# P2N15-001.net
KiCad netlist of a schematic drawn in EAGLE
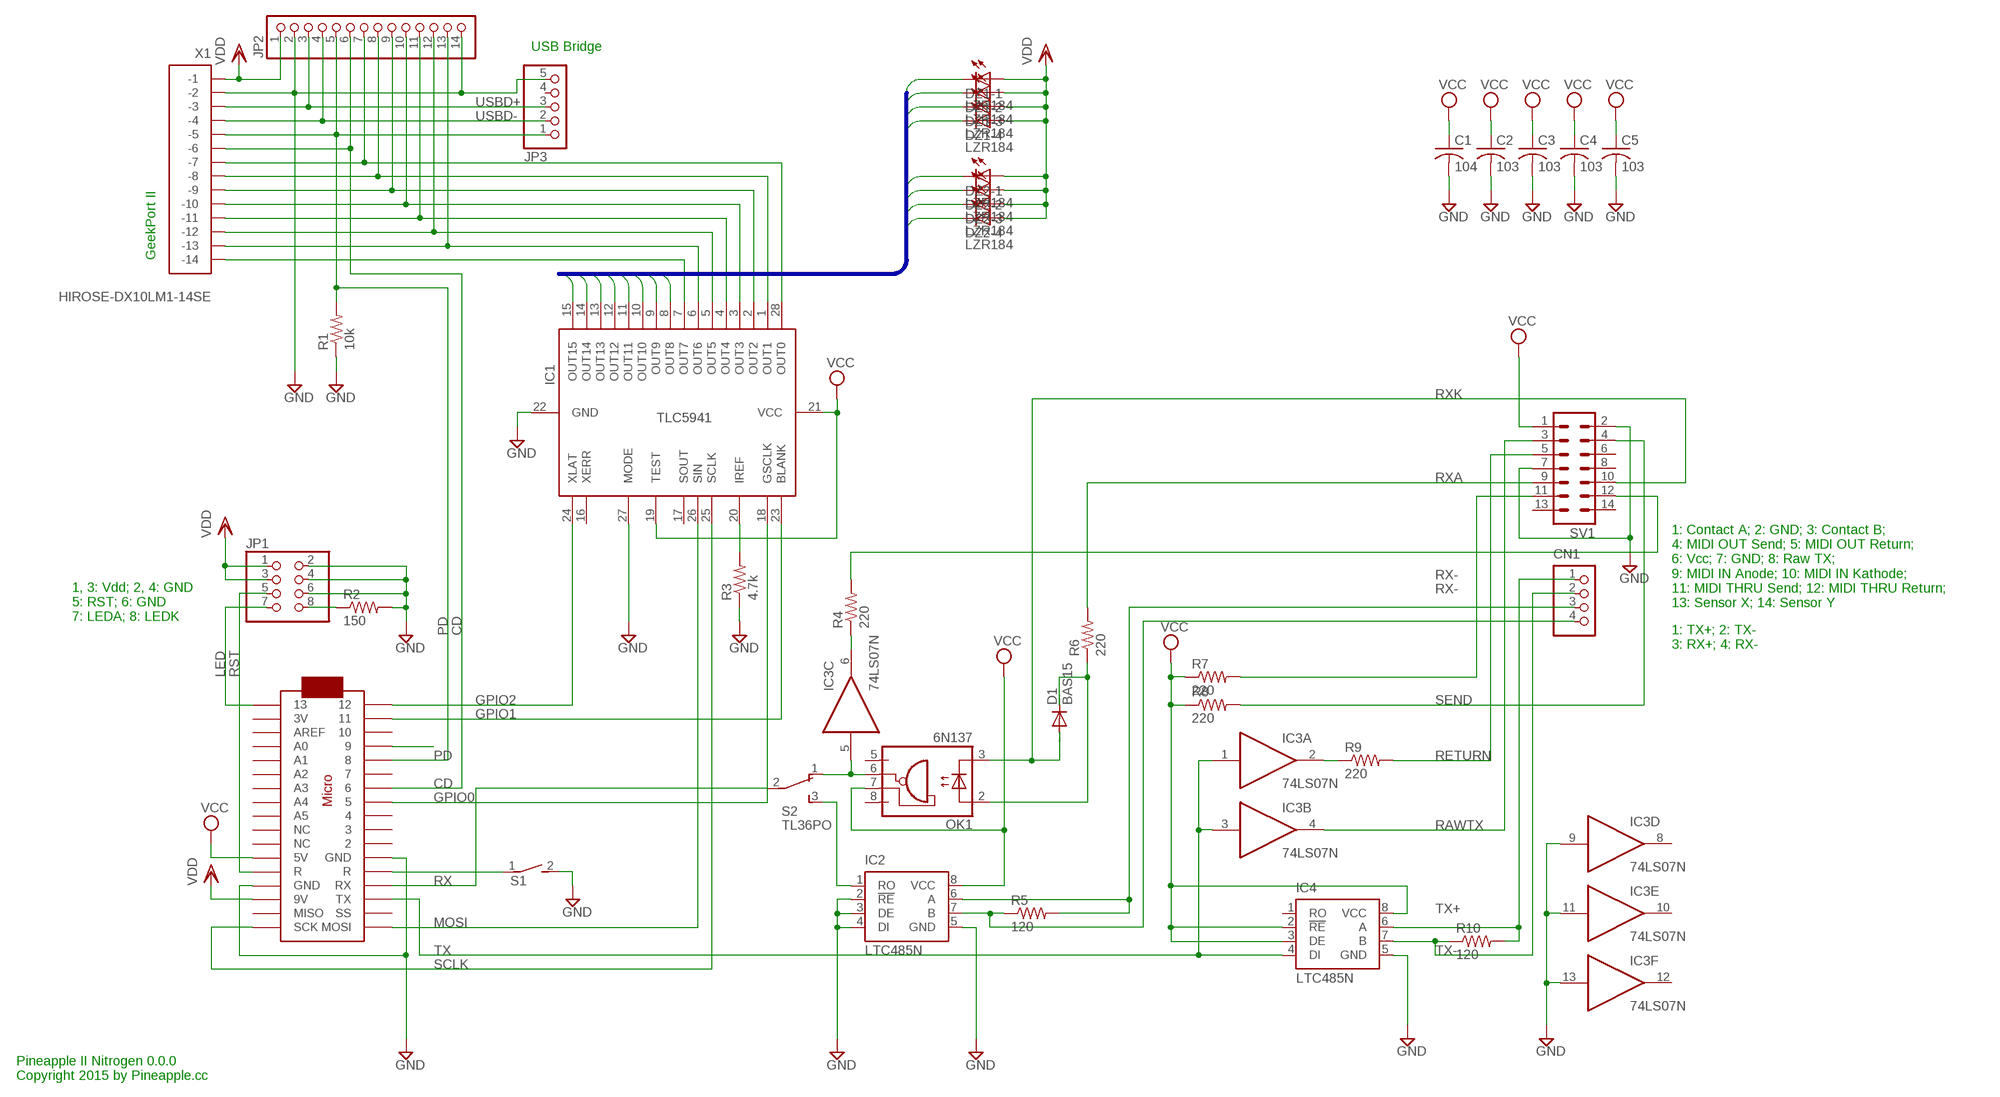
[diagram p0: schematic, sheet 1]

(export (version "E")
  (design (tool "Eeschema 10.0.6"))
  (components
    (comp (ref "C1")
      (value "104")
      (footprint "eagle-import:C025-025X050")
      (libsource (lib "eagle-import") (part "C-US025-025X050"))
    )
    (comp (ref "C2")
      (value "103")
      (footprint "eagle-import:C025-025X050")
      (libsource (lib "eagle-import") (part "C-US025-025X050"))
    )
    (comp (ref "C3")
      (value "103")
      (footprint "eagle-import:C025-025X050")
      (libsource (lib "eagle-import") (part "C-US025-025X050"))
    )
    (comp (ref "C4")
      (value "103")
      (footprint "eagle-import:C025-025X050")
      (libsource (lib "eagle-import") (part "C-US025-025X050"))
    )
    (comp (ref "C5")
      (value "103")
      (footprint "eagle-import:C025-025X050")
      (libsource (lib "eagle-import") (part "C-US025-025X050"))
    )
    (comp (ref "CN1")
      (value "S4B-PH-K-S")
      (footprint "eagle-import:S4B-PH-K-S")
      (libsource (lib "eagle-import") (part "S4B-PH-K-S"))
    )
    (comp (ref "D1")
      (value "BAS15")
      (footprint "eagle-import:DO34-7")
      (libsource (lib "eagle-import") (part "BAS15"))
    )
    (comp (ref "DZ1")
      (value "LZR184")
      (footprint "eagle-import:LZR184")
      (libsource (lib "eagle-import") (part "LZR184"))
    )
    (comp (ref "DZ2")
      (value "LZR184")
      (footprint "eagle-import:LZR184")
      (libsource (lib "eagle-import") (part "LZR184"))
    )
    (comp (ref "IC1")
      (value "TLC5941NT")
      (footprint "eagle-import:DIL28-3")
      (libsource (lib "eagle-import") (part "TLC5941NT"))
    )
    (comp (ref "IC2")
      (value "LTC485N")
      (footprint "eagle-import:DIL08")
      (libsource (lib "eagle-import") (part "LTC485N"))
    )
    (comp (ref "IC3")
      (value "74LS07N")
      (footprint "eagle-import:DIL14")
      (libsource (lib "eagle-import") (part "7407NLS"))
    )
    (comp (ref "IC4")
      (value "LTC485N")
      (footprint "eagle-import:DIL08")
      (libsource (lib "eagle-import") (part "LTC485N"))
    )
    (comp (ref "JP1")
      (value "PINHD-2X4")
      (footprint "eagle-import:2X04")
      (libsource (lib "eagle-import") (part "PINHD-2X4"))
    )
    (comp (ref "JP2")
      (value "PINHD-1X14")
      (footprint "eagle-import:1X14")
      (libsource (lib "eagle-import") (part "PINHD-1X14"))
    )
    (comp (ref "JP3")
      (value "PINHD-1X5/90")
      (footprint "eagle-import:1X05_90")
      (libsource (lib "eagle-import") (part "PINHD-1X5/90"))
    )
    (comp (ref "MC1")
      (value "ARDUINOMICRO")
      (footprint "eagle-import:ARDUINOMICRO")
      (libsource (lib "eagle-import") (part "ARDUINOMICRO"))
    )
    (comp (ref "OK1")
      (value "6N137")
      (footprint "eagle-import:DIL08")
      (libsource (lib "eagle-import") (part "6N137"))
    )
    (comp (ref "R1")
      (value "10k")
      (footprint "eagle-import:0204_5")
      (libsource (lib "eagle-import") (part "R-US_0204/5"))
    )
    (comp (ref "R2")
      (value "150")
      (footprint "eagle-import:0204_5")
      (libsource (lib "eagle-import") (part "R-US_0204/5"))
    )
    (comp (ref "R3")
      (value "4.7k")
      (footprint "eagle-import:0204_5")
      (libsource (lib "eagle-import") (part "R-US_0204/5"))
    )
    (comp (ref "R4")
      (value "220")
      (footprint "eagle-import:0204_5")
      (libsource (lib "eagle-import") (part "R-US_0204/5"))
    )
    (comp (ref "R5")
      (value "120")
      (footprint "eagle-import:0204_5")
      (libsource (lib "eagle-import") (part "R-US_0204/5"))
    )
    (comp (ref "R6")
      (value "220")
      (footprint "eagle-import:0204_5")
      (libsource (lib "eagle-import") (part "R-US_0204/5"))
    )
    (comp (ref "R7")
      (value "220")
      (footprint "eagle-import:0204_5")
      (libsource (lib "eagle-import") (part "R-US_0204/5"))
    )
    (comp (ref "R8")
      (value "220")
      (footprint "eagle-import:0204_5")
      (libsource (lib "eagle-import") (part "R-US_0204/5"))
    )
    (comp (ref "R9")
      (value "220")
      (footprint "eagle-import:0204_5")
      (libsource (lib "eagle-import") (part "R-US_0204/5"))
    )
    (comp (ref "R10")
      (value "120")
      (footprint "eagle-import:0204_5")
      (libsource (lib "eagle-import") (part "R-US_0204/5"))
    )
    (comp (ref "S1")
      (value "DS01E")
      (footprint "eagle-import:DS-01")
      (libsource (lib "eagle-import") (part "DS01E"))
    )
    (comp (ref "S2")
      (value "TL36PO")
      (footprint "eagle-import:TL3XPO")
      (libsource (lib "eagle-import") (part "TL36PO"))
    )
    (comp (ref "SV1")
      (value "ML14L")
      (footprint "eagle-import:ML14L")
      (libsource (lib "eagle-import") (part "ML14L"))
    )
    (comp (ref "X1")
      (value "HIROSE-DX10LM1-14SE")
      (footprint "eagle-import:HIROSE-DX10LM1-14SE")
      (fields (field (name "MPN") "AXR30545"))
      (libsource (lib "eagle-import") (part "HIROSE-DX10LM1-14SE"))
    )
  )
  (nets
    (net (code "1") (name "/CD") (class "Default")
      (node (ref "JP2") (pin "6") (pinfunction "6_6") (pintype "passive"))
      (node (ref "MC1") (pin "P$7") (pinfunction "6_P$7") (pintype "bidirectional"))
      (node (ref "X1") (pin "P$6") (pinfunction "-6_P$6") (pintype "input"))
    )
    (net (code "2") (name "/GPIO0") (class "Default")
      (node (ref "IC1") (pin "18") (pinfunction "GSCLK_18") (pintype "input"))
      (node (ref "MC1") (pin "P$8") (pinfunction "5_P$8") (pintype "bidirectional"))
    )
    (net (code "3") (name "/GPIO1") (class "Default")
      (node (ref "IC1") (pin "23") (pinfunction "BLANK_23") (pintype "input"))
      (node (ref "MC1") (pin "P$2") (pinfunction "11_P$2") (pintype "bidirectional"))
    )
    (net (code "4") (name "/GPIO2") (class "Default")
      (node (ref "IC1") (pin "24") (pinfunction "XLAT_24") (pintype "input"))
      (node (ref "MC1") (pin "P$1") (pinfunction "12_P$1") (pintype "bidirectional"))
    )
    (net (code "5") (name "/LED") (class "Default")
      (node (ref "JP1") (pin "7") (pinfunction "7_7") (pintype "passive"))
      (node (ref "MC1") (pin "P$34") (pinfunction "13_P$34") (pintype "bidirectional"))
    )
    (net (code "6") (name "/LED0") (class "Default")
      (node (ref "DZ1") (pin "K1") (pinfunction "C_K1") (pintype "passive"))
      (node (ref "IC1") (pin "8") (pinfunction "OUT8_8") (pintype "output"))
    )
    (net (code "7") (name "/LED1") (class "Default")
      (node (ref "DZ1") (pin "K2") (pinfunction "C_K2") (pintype "passive"))
      (node (ref "IC1") (pin "9") (pinfunction "OUT9_9") (pintype "output"))
    )
    (net (code "8") (name "/LED2") (class "Default")
      (node (ref "DZ1") (pin "K3") (pinfunction "C_K3") (pintype "passive"))
      (node (ref "IC1") (pin "10") (pinfunction "OUT10_10") (pintype "output"))
    )
    (net (code "9") (name "/LED3") (class "Default")
      (node (ref "DZ1") (pin "K4") (pinfunction "C_K4") (pintype "passive"))
      (node (ref "IC1") (pin "11") (pinfunction "OUT11_11") (pintype "output"))
    )
    (net (code "10") (name "/LED4") (class "Default")
      (node (ref "DZ2") (pin "K1") (pinfunction "C_K1") (pintype "passive"))
      (node (ref "IC1") (pin "12") (pinfunction "OUT12_12") (pintype "output"))
    )
    (net (code "11") (name "/LED5") (class "Default")
      (node (ref "DZ2") (pin "K2") (pinfunction "C_K2") (pintype "passive"))
      (node (ref "IC1") (pin "13") (pinfunction "OUT13_13") (pintype "output"))
    )
    (net (code "12") (name "/LED6") (class "Default")
      (node (ref "DZ2") (pin "K3") (pinfunction "C_K3") (pintype "passive"))
      (node (ref "IC1") (pin "14") (pinfunction "OUT14_14") (pintype "output"))
    )
    (net (code "13") (name "/LED7") (class "Default")
      (node (ref "DZ2") (pin "K4") (pinfunction "C_K4") (pintype "passive"))
      (node (ref "IC1") (pin "15") (pinfunction "OUT15_15") (pintype "output"))
    )
    (net (code "14") (name "/MOSI") (class "Default")
      (node (ref "IC1") (pin "26") (pinfunction "SIN_26") (pintype "input"))
      (node (ref "MC1") (pin "P$17") (pinfunction "MOSI_P$17") (pintype "bidirectional"))
    )
    (net (code "15") (name "/PD") (class "Default")
      (node (ref "JP2") (pin "5") (pinfunction "5_5") (pintype "passive"))
      (node (ref "JP3") (pin "1") (pinfunction "1_1") (pintype "passive"))
      (node (ref "MC1") (pin "P$5") (pinfunction "8_P$5") (pintype "bidirectional"))
      (node (ref "R1") (pin "2") (pinfunction "2_2") (pintype "passive"))
      (node (ref "X1") (pin "P$5") (pinfunction "-5_P$5") (pintype "input"))
    )
    (net (code "16") (name "/RAWTX") (class "Default")
      (node (ref "IC3") (pin "4") (pinfunction "O_4") (pintype "open_collector"))
      (node (ref "SV1") (pin "3") (pinfunction "3_3") (pintype "passive"))
    )
    (net (code "17") (name "/RETURN") (class "Default")
      (node (ref "R9") (pin "2") (pinfunction "2_2") (pintype "passive"))
      (node (ref "SV1") (pin "5") (pinfunction "5_5") (pintype "passive"))
    )
    (net (code "18") (name "/RST") (class "Default")
      (node (ref "JP1") (pin "5") (pinfunction "5_5") (pintype "passive"))
      (node (ref "MC1") (pin "P$13") (pinfunction "R_P$13") (pintype "bidirectional"))
    )
    (net (code "19") (name "/RX") (class "Default")
      (node (ref "MC1") (pin "P$14") (pinfunction "RX_P$14") (pintype "bidirectional"))
      (node (ref "S2") (pin "2") (pinfunction "P_2") (pintype "passive"))
    )
    (net (code "20") (name "/RX-") (class "Default")
      (node (ref "CN1") (pin "4") (pinfunction "4_4") (pintype "passive"))
      (node (ref "IC2") (pin "7") (pinfunction "B_7") (pintype "bidirectional"))
      (node (ref "R5") (pin "1") (pinfunction "1_1") (pintype "passive"))
    )
    (net (code "21") (name "/RXA") (class "Default")
      (node (ref "R6") (pin "2") (pinfunction "2_2") (pintype "passive"))
      (node (ref "SV1") (pin "9") (pinfunction "9_9") (pintype "passive"))
    )
    (net (code "22") (name "/RXK") (class "Default")
      (node (ref "D1") (pin "A") (pinfunction "A_A") (pintype "passive"))
      (node (ref "OK1") (pin "3") (pinfunction "C_3") (pintype "passive"))
      (node (ref "SV1") (pin "10") (pinfunction "10_10") (pintype "passive"))
    )
    (net (code "23") (name "/SCLK") (class "Default")
      (node (ref "IC1") (pin "25") (pinfunction "SCLK_25") (pintype "input"))
      (node (ref "MC1") (pin "P$18") (pinfunction "SCK_P$18") (pintype "bidirectional"))
    )
    (net (code "24") (name "/SEND") (class "Default")
      (node (ref "R8") (pin "2") (pinfunction "2_2") (pintype "passive"))
      (node (ref "SV1") (pin "4") (pinfunction "4_4") (pintype "passive"))
    )
    (net (code "25") (name "/TX") (class "Default")
      (node (ref "IC3") (pin "1") (pinfunction "I_1") (pintype "input"))
      (node (ref "IC3") (pin "3") (pinfunction "I_3") (pintype "input"))
      (node (ref "IC4") (pin "4") (pinfunction "DI_4") (pintype "input"))
      (node (ref "MC1") (pin "P$15") (pinfunction "TX_P$15") (pintype "bidirectional"))
    )
    (net (code "26") (name "/TX+") (class "Default")
      (node (ref "CN1") (pin "1") (pinfunction "1_1") (pintype "passive"))
      (node (ref "IC4") (pin "6") (pinfunction "A_6") (pintype "bidirectional"))
      (node (ref "R10") (pin "2") (pinfunction "2_2") (pintype "passive"))
    )
    (net (code "27") (name "/TX-") (class "Default")
      (node (ref "CN1") (pin "2") (pinfunction "2_2") (pintype "passive"))
      (node (ref "IC4") (pin "7") (pinfunction "B_7") (pintype "bidirectional"))
      (node (ref "R10") (pin "1") (pinfunction "1_1") (pintype "passive"))
    )
    (net (code "28") (name "/USBD+") (class "Default")
      (node (ref "JP2") (pin "3") (pinfunction "3_3") (pintype "passive"))
      (node (ref "JP3") (pin "3") (pinfunction "3_3") (pintype "passive"))
      (node (ref "X1") (pin "P$3") (pinfunction "-3_P$3") (pintype "input"))
    )
    (net (code "29") (name "/USBD-") (class "Default")
      (node (ref "JP2") (pin "4") (pinfunction "4_4") (pintype "passive"))
      (node (ref "JP3") (pin "2") (pinfunction "2_2") (pintype "passive"))
      (node (ref "X1") (pin "P$4") (pinfunction "-4_P$4") (pintype "input"))
    )
    (net (code "30") (name "GND") (class "Default")
      (node (ref "C1") (pin "2") (pinfunction "2_2") (pintype "passive"))
      (node (ref "C2") (pin "2") (pinfunction "2_2") (pintype "passive"))
      (node (ref "C3") (pin "2") (pinfunction "2_2") (pintype "passive"))
      (node (ref "C4") (pin "2") (pinfunction "2_2") (pintype "passive"))
      (node (ref "C5") (pin "2") (pinfunction "2_2") (pintype "passive"))
      (node (ref "IC1") (pin "22") (pinfunction "GND_22") (pintype "power_in"))
      (node (ref "IC1") (pin "27") (pinfunction "MODE_27") (pintype "input"))
      (node (ref "IC2") (pin "2") (pinfunction "~{RE}_2") (pintype "input"))
      (node (ref "IC2") (pin "3") (pinfunction "DE_3") (pintype "input"))
      (node (ref "IC2") (pin "4") (pinfunction "DI_4") (pintype "input"))
      (node (ref "IC2") (pin "5") (pinfunction "GND_5") (pintype "input"))
      (node (ref "IC3") (pin "11") (pinfunction "I_11") (pintype "input"))
      (node (ref "IC3") (pin "13") (pinfunction "I_13") (pintype "input"))
      (node (ref "IC3") (pin "9") (pinfunction "I_9") (pintype "input"))
      (node (ref "IC4") (pin "5") (pinfunction "GND_5") (pintype "input"))
      (node (ref "JP1") (pin "2") (pinfunction "2_2") (pintype "passive"))
      (node (ref "JP1") (pin "4") (pinfunction "4_4") (pintype "passive"))
      (node (ref "JP1") (pin "6") (pinfunction "6_6") (pintype "passive"))
      (node (ref "JP2") (pin "14") (pinfunction "14_14") (pintype "passive"))
      (node (ref "JP2") (pin "2") (pinfunction "2_2") (pintype "passive"))
      (node (ref "JP3") (pin "5") (pinfunction "5_5") (pintype "passive"))
      (node (ref "MC1") (pin "P$12") (pinfunction "GND_P$12") (pintype "bidirectional"))
      (node (ref "MC1") (pin "P$21") (pinfunction "GND_P$21") (pintype "bidirectional"))
      (node (ref "R1") (pin "1") (pinfunction "1_1") (pintype "passive"))
      (node (ref "R2") (pin "2") (pinfunction "2_2") (pintype "passive"))
      (node (ref "R3") (pin "1") (pinfunction "1_1") (pintype "passive"))
      (node (ref "S1") (pin "2") (pinfunction "2_2") (pintype "passive"))
      (node (ref "SV1") (pin "2") (pinfunction "2_2") (pintype "passive"))
      (node (ref "SV1") (pin "7") (pinfunction "7_7") (pintype "passive"))
      (node (ref "X1") (pin "P$2") (pinfunction "-2_P$2") (pintype "input"))
    )
    (net (code "31") (name "Net-(IC1-IREF)") (class "Default")
      (node (ref "IC1") (pin "20") (pinfunction "IREF_20") (pintype "bidirectional"))
      (node (ref "R3") (pin "2") (pinfunction "2_2") (pintype "passive"))
    )
    (net (code "32") (name "Net-(IC1-OUT0)") (class "Default")
      (node (ref "IC1") (pin "28") (pinfunction "OUT0_28") (pintype "output"))
      (node (ref "JP2") (pin "7") (pinfunction "7_7") (pintype "passive"))
      (node (ref "X1") (pin "P$7") (pinfunction "-7_P$7") (pintype "input"))
    )
    (net (code "33") (name "Net-(IC1-OUT1)") (class "Default")
      (node (ref "IC1") (pin "1") (pinfunction "OUT1_1") (pintype "output"))
      (node (ref "JP2") (pin "8") (pinfunction "8_8") (pintype "passive"))
      (node (ref "X1") (pin "P$8") (pinfunction "-8_P$8") (pintype "input"))
    )
    (net (code "34") (name "Net-(IC1-OUT2)") (class "Default")
      (node (ref "IC1") (pin "2") (pinfunction "OUT2_2") (pintype "output"))
      (node (ref "JP2") (pin "9") (pinfunction "9_9") (pintype "passive"))
      (node (ref "X1") (pin "P$9") (pinfunction "-9_P$9") (pintype "input"))
    )
    (net (code "35") (name "Net-(IC1-OUT3)") (class "Default")
      (node (ref "IC1") (pin "3") (pinfunction "OUT3_3") (pintype "output"))
      (node (ref "JP2") (pin "10") (pinfunction "10_10") (pintype "passive"))
      (node (ref "X1") (pin "P$10") (pinfunction "-10_P$10") (pintype "input"))
    )
    (net (code "36") (name "Net-(IC1-OUT4)") (class "Default")
      (node (ref "IC1") (pin "4") (pinfunction "OUT4_4") (pintype "output"))
      (node (ref "JP2") (pin "11") (pinfunction "11_11") (pintype "passive"))
      (node (ref "X1") (pin "P$11") (pinfunction "-11_P$11") (pintype "input"))
    )
    (net (code "37") (name "Net-(IC1-OUT5)") (class "Default")
      (node (ref "IC1") (pin "5") (pinfunction "OUT5_5") (pintype "output"))
      (node (ref "JP2") (pin "12") (pinfunction "12_12") (pintype "passive"))
      (node (ref "X1") (pin "P$12") (pinfunction "-12_P$12") (pintype "input"))
    )
    (net (code "38") (name "Net-(IC1-OUT6)") (class "Default")
      (node (ref "IC1") (pin "6") (pinfunction "OUT6_6") (pintype "output"))
      (node (ref "JP2") (pin "13") (pinfunction "13_13") (pintype "passive"))
      (node (ref "X1") (pin "P$13") (pinfunction "-13_P$13") (pintype "input"))
    )
    (net (code "39") (name "Net-(IC1-OUT7)") (class "Default")
      (node (ref "IC1") (pin "7") (pinfunction "OUT7_7") (pintype "output"))
      (node (ref "X1") (pin "P$14") (pinfunction "-14_P$14") (pintype "input"))
    )
    (net (code "40") (name "Net-(IC2-A)") (class "Default")
      (node (ref "CN1") (pin "3") (pinfunction "3_3") (pintype "passive"))
      (node (ref "IC2") (pin "6") (pinfunction "A_6") (pintype "bidirectional"))
      (node (ref "R5") (pin "2") (pinfunction "2_2") (pintype "passive"))
    )
    (net (code "41") (name "Net-(IC2-RO)") (class "Default")
      (node (ref "IC2") (pin "1") (pinfunction "RO_1") (pintype "output"))
      (node (ref "S2") (pin "3") (pinfunction "S_3") (pintype "passive"))
    )
    (net (code "42") (name "Net-(IC3A-O)") (class "Default")
      (node (ref "IC3") (pin "2") (pinfunction "O_2") (pintype "open_collector"))
      (node (ref "R9") (pin "1") (pinfunction "1_1") (pintype "passive"))
    )
    (net (code "43") (name "Net-(IC3C-I)") (class "Default")
      (node (ref "IC3") (pin "5") (pinfunction "I_5") (pintype "input"))
      (node (ref "OK1") (pin "6") (pinfunction "VO_6") (pintype "passive"))
      (node (ref "S2") (pin "1") (pinfunction "O_1") (pintype "passive"))
    )
    (net (code "44") (name "Net-(IC3C-O)") (class "Default")
      (node (ref "IC3") (pin "6") (pinfunction "O_6") (pintype "open_collector"))
      (node (ref "R4") (pin "1") (pinfunction "1_1") (pintype "passive"))
    )
    (net (code "45") (name "Net-(JP1-Pad8)") (class "Default")
      (node (ref "JP1") (pin "8") (pinfunction "8_8") (pintype "passive"))
      (node (ref "R2") (pin "1") (pinfunction "1_1") (pintype "passive"))
    )
    (net (code "46") (name "Net-(MC1-R-PadP$22)") (class "Default")
      (node (ref "MC1") (pin "P$22") (pinfunction "R_P$22") (pintype "bidirectional"))
      (node (ref "S1") (pin "1") (pinfunction "1_1") (pintype "passive"))
    )
    (net (code "47") (name "Net-(OK1-A)") (class "Default")
      (node (ref "D1") (pin "C") (pinfunction "C_C") (pintype "passive"))
      (node (ref "OK1") (pin "2") (pinfunction "A_2") (pintype "passive"))
      (node (ref "R6") (pin "1") (pinfunction "1_1") (pintype "passive"))
    )
    (net (code "48") (name "Net-(R4-Pad2)") (class "Default")
      (node (ref "R4") (pin "2") (pinfunction "2_2") (pintype "passive"))
      (node (ref "SV1") (pin "12") (pinfunction "12_12") (pintype "passive"))
    )
    (net (code "49") (name "Net-(R7-Pad2)") (class "Default")
      (node (ref "R7") (pin "2") (pinfunction "2_2") (pintype "passive"))
      (node (ref "SV1") (pin "11") (pinfunction "11_11") (pintype "passive"))
    )
    (net (code "50") (name "VCC") (class "Default")
      (node (ref "C1") (pin "1") (pinfunction "1_1") (pintype "passive"))
      (node (ref "C2") (pin "1") (pinfunction "1_1") (pintype "passive"))
      (node (ref "C3") (pin "1") (pinfunction "1_1") (pintype "passive"))
      (node (ref "C4") (pin "1") (pinfunction "1_1") (pintype "passive"))
      (node (ref "C5") (pin "1") (pinfunction "1_1") (pintype "passive"))
      (node (ref "IC1") (pin "19") (pinfunction "TEST_19") (pintype "input"))
      (node (ref "IC1") (pin "21") (pinfunction "VCC_21") (pintype "power_in"))
      (node (ref "IC2") (pin "8") (pinfunction "VCC_8") (pintype "input"))
      (node (ref "IC4") (pin "2") (pinfunction "~{RE}_2") (pintype "input"))
      (node (ref "IC4") (pin "3") (pinfunction "DE_3") (pintype "input"))
      (node (ref "IC4") (pin "8") (pinfunction "VCC_8") (pintype "input"))
      (node (ref "MC1") (pin "P$23") (pinfunction "5V_P$23") (pintype "bidirectional"))
      (node (ref "OK1") (pin "7") (pinfunction "VE_7") (pintype "passive"))
      (node (ref "R7") (pin "1") (pinfunction "1_1") (pintype "passive"))
      (node (ref "R8") (pin "1") (pinfunction "1_1") (pintype "passive"))
      (node (ref "SV1") (pin "1") (pinfunction "1_1") (pintype "passive"))
    )
    (net (code "51") (name "VDD") (class "Default")
      (node (ref "DZ1") (pin "A1") (pinfunction "A_A1") (pintype "passive"))
      (node (ref "DZ1") (pin "A2") (pinfunction "A_A2") (pintype "passive"))
      (node (ref "DZ1") (pin "A3") (pinfunction "A_A3") (pintype "passive"))
      (node (ref "DZ1") (pin "A4") (pinfunction "A_A4") (pintype "passive"))
      (node (ref "DZ2") (pin "A1") (pinfunction "A_A1") (pintype "passive"))
      (node (ref "DZ2") (pin "A2") (pinfunction "A_A2") (pintype "passive"))
      (node (ref "DZ2") (pin "A3") (pinfunction "A_A3") (pintype "passive"))
      (node (ref "DZ2") (pin "A4") (pinfunction "A_A4") (pintype "passive"))
      (node (ref "JP1") (pin "1") (pinfunction "1_1") (pintype "passive"))
      (node (ref "JP1") (pin "3") (pinfunction "3_3") (pintype "passive"))
      (node (ref "JP2") (pin "1") (pinfunction "1_1") (pintype "passive"))
      (node (ref "MC1") (pin "P$20") (pinfunction "9V_P$20") (pintype "bidirectional"))
      (node (ref "X1") (pin "P$1") (pinfunction "-1_P$1") (pintype "input"))
    )
    (net (code "52") (name "unconnected-(IC1-SOUT-Pad17)") (class "Default")
      (node (ref "IC1") (pin "17") (pinfunction "SOUT_17") (pintype "output"))
    )
    (net (code "53") (name "unconnected-(IC1-XERR-Pad16)") (class "Default")
      (node (ref "IC1") (pin "16") (pinfunction "XERR_16") (pintype "output"))
    )
    (net (code "54") (name "unconnected-(IC3D-O-Pad8)") (class "Default")
      (node (ref "IC3") (pin "8") (pinfunction "O_8") (pintype "open_collector"))
    )
    (net (code "55") (name "unconnected-(IC3E-O-Pad10)") (class "Default")
      (node (ref "IC3") (pin "10") (pinfunction "O_10") (pintype "open_collector"))
    )
    (net (code "56") (name "unconnected-(IC3F-O-Pad12)") (class "Default")
      (node (ref "IC3") (pin "12") (pinfunction "O_12") (pintype "open_collector"))
    )
    (net (code "57") (name "unconnected-(IC4-RO-Pad1)") (class "Default")
      (node (ref "IC4") (pin "1") (pinfunction "RO_1") (pintype "output"))
    )
    (net (code "58") (name "unconnected-(JP3-Pad4)") (class "Default")
      (node (ref "JP3") (pin "4") (pinfunction "4_4") (pintype "passive"))
    )
    (net (code "59") (name "unconnected-(MC1-2-PadP$11)") (class "Default")
      (node (ref "MC1") (pin "P$11") (pinfunction "2_P$11") (pintype "bidirectional"))
    )
    (net (code "60") (name "unconnected-(MC1-3-PadP$10)") (class "Default")
      (node (ref "MC1") (pin "P$10") (pinfunction "3_P$10") (pintype "bidirectional"))
    )
    (net (code "61") (name "unconnected-(MC1-3V-PadP$33)") (class "Default")
      (node (ref "MC1") (pin "P$33") (pinfunction "3V_P$33") (pintype "bidirectional"))
    )
    (net (code "62") (name "unconnected-(MC1-4-PadP$9)") (class "Default")
      (node (ref "MC1") (pin "P$9") (pinfunction "4_P$9") (pintype "bidirectional"))
    )
    (net (code "63") (name "unconnected-(MC1-7-PadP$6)") (class "Default")
      (node (ref "MC1") (pin "P$6") (pinfunction "7_P$6") (pintype "bidirectional"))
    )
    (net (code "64") (name "unconnected-(MC1-9-PadP$4)") (class "Default")
      (node (ref "MC1") (pin "P$4") (pinfunction "9_P$4") (pintype "bidirectional"))
    )
    (net (code "65") (name "unconnected-(MC1-10-PadP$3)") (class "Default")
      (node (ref "MC1") (pin "P$3") (pinfunction "10_P$3") (pintype "bidirectional"))
    )
    (net (code "66") (name "unconnected-(MC1-A0-PadP$31)") (class "Default")
      (node (ref "MC1") (pin "P$31") (pinfunction "A0_P$31") (pintype "bidirectional"))
    )
    (net (code "67") (name "unconnected-(MC1-A1-PadP$30)") (class "Default")
      (node (ref "MC1") (pin "P$30") (pinfunction "A1_P$30") (pintype "bidirectional"))
    )
    (net (code "68") (name "unconnected-(MC1-A2-PadP$29)") (class "Default")
      (node (ref "MC1") (pin "P$29") (pinfunction "A2_P$29") (pintype "bidirectional"))
    )
    (net (code "69") (name "unconnected-(MC1-A3-PadP$28)") (class "Default")
      (node (ref "MC1") (pin "P$28") (pinfunction "A3_P$28") (pintype "bidirectional"))
    )
    (net (code "70") (name "unconnected-(MC1-A4-PadP$27)") (class "Default")
      (node (ref "MC1") (pin "P$27") (pinfunction "A4_P$27") (pintype "bidirectional"))
    )
    (net (code "71") (name "unconnected-(MC1-A5-PadP$26)") (class "Default")
      (node (ref "MC1") (pin "P$26") (pinfunction "A5_P$26") (pintype "bidirectional"))
    )
    (net (code "72") (name "unconnected-(MC1-AREF-PadP$32)") (class "Default")
      (node (ref "MC1") (pin "P$32") (pinfunction "AREF_P$32") (pintype "bidirectional"))
    )
    (net (code "73") (name "unconnected-(MC1-MISO-PadP$19)") (class "Default")
      (node (ref "MC1") (pin "P$19") (pinfunction "MISO_P$19") (pintype "bidirectional"))
    )
    (net (code "74") (name "unconnected-(MC1-NC-PadP$24)") (class "Default")
      (node (ref "MC1") (pin "P$24") (pinfunction "NC_P$24") (pintype "bidirectional"))
    )
    (net (code "75") (name "unconnected-(MC1-NC-PadP$25)") (class "Default")
      (node (ref "MC1") (pin "P$25") (pinfunction "NC_P$25") (pintype "bidirectional"))
    )
    (net (code "76") (name "unconnected-(MC1-SS-PadP$16)") (class "Default")
      (node (ref "MC1") (pin "P$16") (pinfunction "SS_P$16") (pintype "bidirectional"))
    )
    (net (code "77") (name "unconnected-(OK1-GND-Pad5)") (class "Default")
      (node (ref "OK1") (pin "5") (pinfunction "GND_5") (pintype "passive"))
    )
    (net (code "78") (name "unconnected-(OK1-VCC-Pad8)") (class "Default")
      (node (ref "OK1") (pin "8") (pinfunction "VCC_8") (pintype "passive"))
    )
    (net (code "79") (name "unconnected-(SV1-Pad6)") (class "Default")
      (node (ref "SV1") (pin "6") (pinfunction "6_6") (pintype "passive"))
    )
    (net (code "80") (name "unconnected-(SV1-Pad8)") (class "Default")
      (node (ref "SV1") (pin "8") (pinfunction "8_8") (pintype "passive"))
    )
    (net (code "81") (name "unconnected-(SV1-Pad13)") (class "Default")
      (node (ref "SV1") (pin "13") (pinfunction "13_13") (pintype "passive"))
    )
    (net (code "82") (name "unconnected-(SV1-Pad14)") (class "Default")
      (node (ref "SV1") (pin "14") (pinfunction "14_14") (pintype "passive"))
    )
  )
)
